# samd21_sensorhub_1_1_1_jan2022.net
KiCad netlist of a schematic drawn in EAGLE
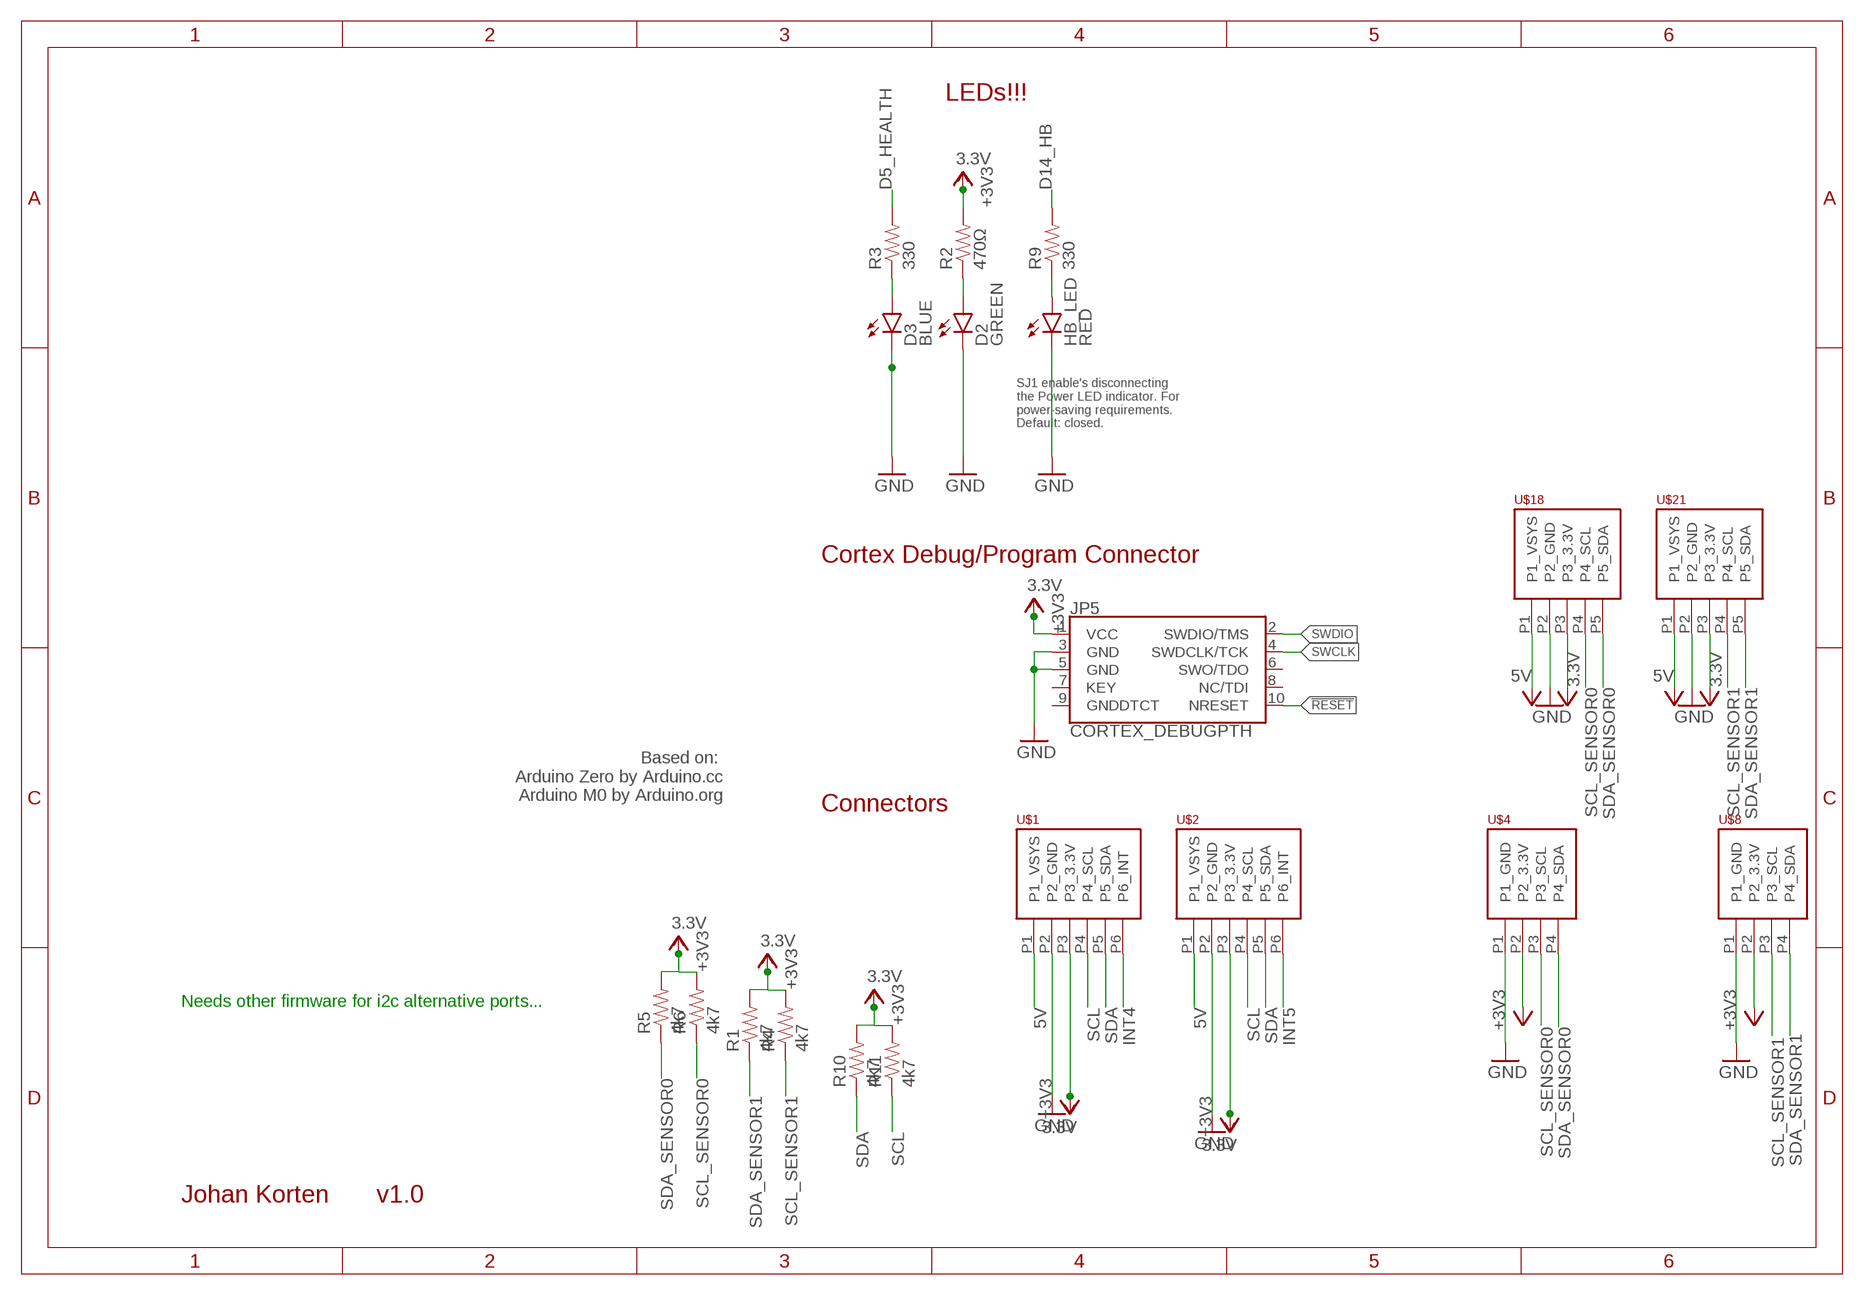
[diagram p0: schematic, sheet 1]
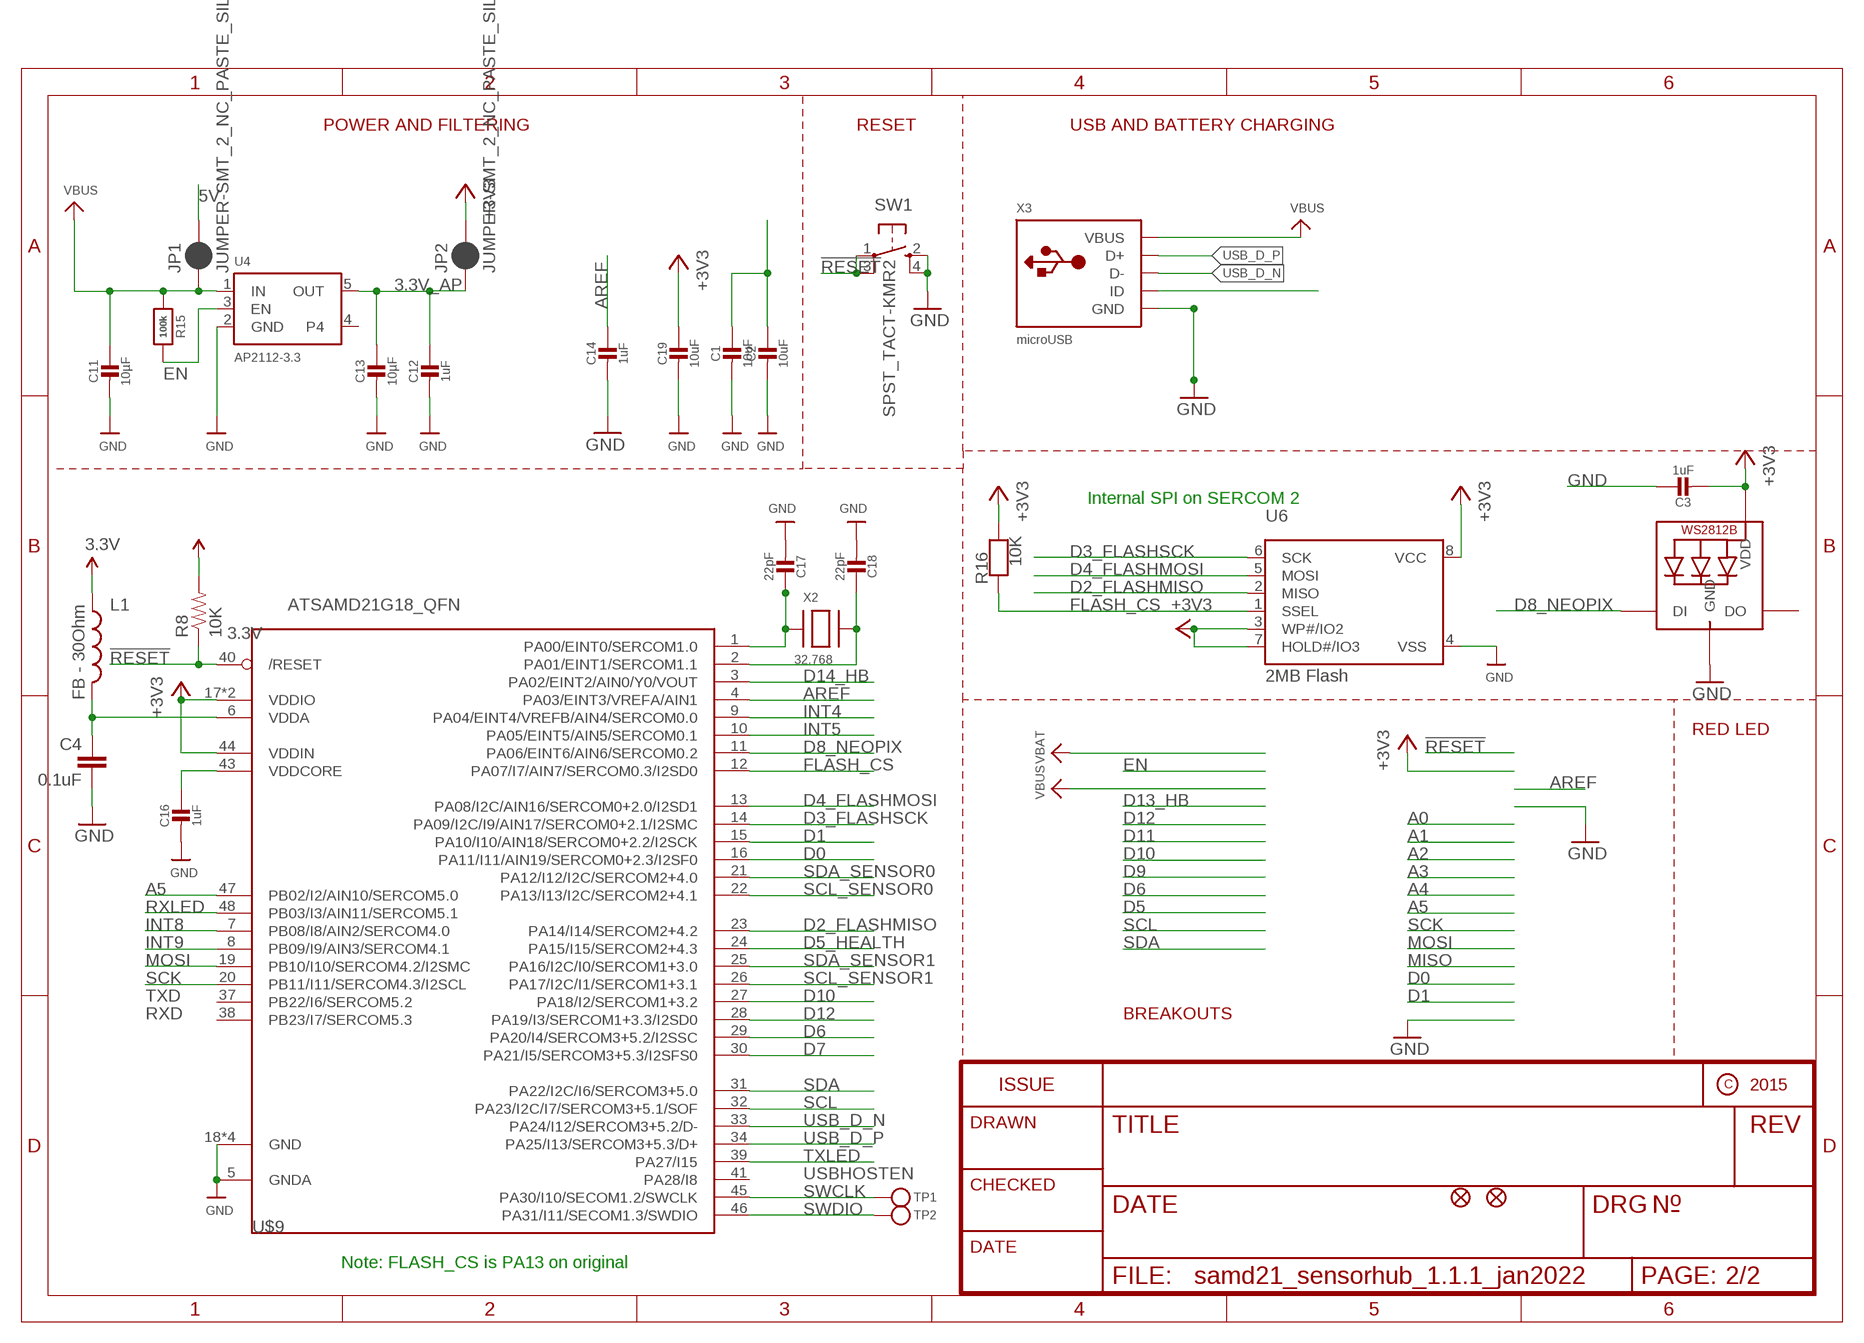
[diagram p1: schematic, sheet 2]

(export (version "E")
  (design (tool "Eeschema 10.0.6"))
  (components
    (comp (ref "D2")
      (value "GREEN")
      (footprint "eagle-import:LED-0603")
      (libsource (lib "eagle-import") (part "LED-RED0603"))
    )
    (comp (ref "D3")
      (value "BLUE")
      (footprint "eagle-import:LED-0603")
      (libsource (lib "eagle-import") (part "LED-BLUE0603"))
    )
    (comp (ref "HB_LED")
      (value "RED")
      (footprint "eagle-import:LED-0603")
      (libsource (lib "eagle-import") (part "LED-RED0603"))
    )
    (comp (ref "JP5")
      (value "CORTEX_DEBUGPTH")
      (footprint "eagle-import:2X5-PTH-1.27MM")
      (libsource (lib "eagle-import") (part "CORTEX_DEBUGPTH"))
    )
    (comp (ref "R1")
      (value "4k7")
      (footprint "eagle-import:0603-RES")
      (libsource (lib "eagle-import") (part "330OHM1/10W1%(0603)"))
    )
    (comp (ref "R2")
      (value "470Ω")
      (footprint "eagle-import:0603-RES")
      (libsource (lib "eagle-import") (part "330OHM1/10W1%(0603)"))
    )
    (comp (ref "R3")
      (value "330")
      (footprint "eagle-import:0603-RES")
      (libsource (lib "eagle-import") (part "330OHM1/10W1%(0603)"))
    )
    (comp (ref "R4")
      (value "4k7")
      (footprint "eagle-import:0603-RES")
      (libsource (lib "eagle-import") (part "330OHM1/10W1%(0603)"))
    )
    (comp (ref "R5")
      (value "4k7")
      (footprint "eagle-import:0603-RES")
      (libsource (lib "eagle-import") (part "330OHM1/10W1%(0603)"))
    )
    (comp (ref "R6")
      (value "4k7")
      (footprint "eagle-import:0603-RES")
      (libsource (lib "eagle-import") (part "330OHM1/10W1%(0603)"))
    )
    (comp (ref "R9")
      (value "330")
      (footprint "eagle-import:0603-RES")
      (libsource (lib "eagle-import") (part "330OHM1/10W1%(0603)"))
    )
    (comp (ref "R10")
      (value "4k7")
      (footprint "eagle-import:0603-RES")
      (libsource (lib "eagle-import") (part "330OHM1/10W1%(0603)"))
    )
    (comp (ref "R11")
      (value "4k7")
      (footprint "eagle-import:0603-RES")
      (libsource (lib "eagle-import") (part "330OHM1/10W1%(0603)"))
    )
    (comp (ref "U$1")
      (value "PHOENIX_PTSM_M6_TH_I2CPPANGLE")
      (footprint "eagle-import:PTSM_M6_THRHOLE")
      (libsource (lib "eagle-import") (part "PHOENIX_PTSM_M6_TH_I2CPPANGLE"))
    )
    (comp (ref "U$2")
      (value "PHOENIX_PTSM_M6_TH_I2CPPANGLE")
      (footprint "eagle-import:PTSM_M6_THRHOLE")
      (libsource (lib "eagle-import") (part "PHOENIX_PTSM_M6_TH_I2CPPANGLE"))
    )
    (comp (ref "U$4")
      (value "PHOENIX_PTSM_M4_THANGLE")
      (footprint "eagle-import:PTSM_M4_TH")
      (libsource (lib "eagle-import") (part "PHOENIX_PTSM_M4_THANGLE"))
    )
    (comp (ref "U$8")
      (value "PHOENIX_PTSM_M4_THANGLE")
      (footprint "eagle-import:PTSM_M4_TH")
      (libsource (lib "eagle-import") (part "PHOENIX_PTSM_M4_THANGLE"))
    )
    (comp (ref "U$18")
      (value "PHOENIX_PTSM_M5_TH_I2C++")
      (footprint "eagle-import:PTSM_M5_THRHOLE")
      (libsource (lib "eagle-import") (part "PHOENIX_PTSM_M5_TH_I2C++"))
    )
    (comp (ref "U$21")
      (value "PHOENIX_PTSM_M5_TH_I2C++")
      (footprint "eagle-import:PTSM_M5_THRHOLE")
      (libsource (lib "eagle-import") (part "PHOENIX_PTSM_M5_TH_I2C++"))
    )
    (comp (ref "C1")
      (value "10uF")
      (footprint "eagle-import:0805-NO")
      (libsource (lib "eagle-import") (part "CAP_CERAMIC0805-NOOUTLINE"))
    )
    (comp (ref "C2")
      (value "10uF")
      (footprint "eagle-import:0805-NO")
      (libsource (lib "eagle-import") (part "CAP_CERAMIC0805-NOOUTLINE"))
    )
    (comp (ref "C3")
      (value "1uF")
      (footprint "eagle-import:0603-NO")
      (libsource (lib "eagle-import") (part "CAP_CERAMIC0603_NO"))
    )
    (comp (ref "C4")
      (value "0.1uF")
      (footprint "eagle-import:0402-CAP")
      (libsource (lib "eagle-import") (part "0.1UF-16V(+-10%)(0402)"))
    )
    (comp (ref "C11")
      (value "10µF")
      (footprint "eagle-import:0805-NO")
      (libsource (lib "eagle-import") (part "CAP_CERAMIC0805-NOOUTLINE"))
    )
    (comp (ref "C12")
      (value "1uF")
      (footprint "eagle-import:0603-NO")
      (libsource (lib "eagle-import") (part "CAP_CERAMIC0603_NO"))
    )
    (comp (ref "C13")
      (value "10µF")
      (footprint "eagle-import:0805-NO")
      (libsource (lib "eagle-import") (part "CAP_CERAMIC0805-NOOUTLINE"))
    )
    (comp (ref "C14")
      (value "1uF")
      (footprint "eagle-import:0603-NO")
      (libsource (lib "eagle-import") (part "CAP_CERAMIC0603_NO"))
    )
    (comp (ref "C16")
      (value "1uF")
      (footprint "eagle-import:0603-NO")
      (libsource (lib "eagle-import") (part "CAP_CERAMIC0603_NO"))
    )
    (comp (ref "C17")
      (value "22pF")
      (footprint "eagle-import:0603-NO")
      (libsource (lib "eagle-import") (part "CAP_CERAMIC0603_NO"))
    )
    (comp (ref "C18")
      (value "22pF")
      (footprint "eagle-import:0603-NO")
      (libsource (lib "eagle-import") (part "CAP_CERAMIC0603_NO"))
    )
    (comp (ref "C19")
      (value "10uF")
      (footprint "eagle-import:0805-NO")
      (libsource (lib "eagle-import") (part "CAP_CERAMIC0805-NOOUTLINE"))
    )
    (comp (ref "JP1")
      (value "JUMPER-SMT_2_NC_PASTE_SILK")
      (footprint "eagle-import:SMT-JUMPER_2_NC_PASTE_SILK")
      (libsource (lib "eagle-import") (part "JUMPER-SMT_2_NC_PASTE_SILK"))
    )
    (comp (ref "JP2")
      (value "JUMPER-SMT_2_NC_PASTE_SILK")
      (footprint "eagle-import:SMT-JUMPER_2_NC_PASTE_SILK")
      (libsource (lib "eagle-import") (part "JUMPER-SMT_2_NC_PASTE_SILK"))
    )
    (comp (ref "L1")
      (value "FB - 30Ohm")
      (footprint "eagle-import:0603")
      (libsource (lib "eagle-import") (part "INDUCTOR0603"))
    )
    (comp (ref "LED1")
      (value "WS2812B3535")
      (footprint "eagle-import:LED3535")
      (libsource (lib "eagle-import") (part "WS2812B3535"))
    )
    (comp (ref "R8")
      (value "10K")
      (footprint "eagle-import:0603-RES")
      (libsource (lib "eagle-import") (part "10KOHM-1/10W-1%(0603)0603"))
    )
    (comp (ref "R15")
      (value "100k")
      (footprint "eagle-import:0603-NO")
      (libsource (lib "eagle-import") (part "RESISTOR_0603_NOOUT"))
    )
    (comp (ref "R16")
      (value "10K")
      (footprint "eagle-import:0603-NO")
      (libsource (lib "eagle-import") (part "RESISTOR_0603_NOOUT"))
    )
    (comp (ref "SW1")
      (value "SPST_TACT-KMR2")
      (footprint "eagle-import:KMR2")
      (libsource (lib "eagle-import") (part "SPST_TACT-KMR2"))
    )
    (comp (ref "TP1")
      (value "TESTPOINTROUND1.5MM")
      (footprint "eagle-import:TESTPOINT_ROUND_1.5MM")
      (libsource (lib "eagle-import") (part "TESTPOINTROUND1.5MM"))
    )
    (comp (ref "TP2")
      (value "TESTPOINTROUND1.5MM")
      (footprint "eagle-import:TESTPOINT_ROUND_1.5MM")
      (libsource (lib "eagle-import") (part "TESTPOINTROUND1.5MM"))
    )
    (comp (ref "U$9")
      (value "ATSAMD21G18_QFN")
      (footprint "eagle-import:TQFN48_7MM")
      (libsource (lib "eagle-import") (part "ATSAMD21G_QFN"))
    )
    (comp (ref "U$34")
      (value "FIDUCIAL\"\"")
      (footprint "eagle-import:FIDUCIAL_1MM")
      (libsource (lib "eagle-import") (part "FIDUCIAL{dblquote}{dblquote}"))
    )
    (comp (ref "U$35")
      (value "FIDUCIAL\"\"")
      (footprint "eagle-import:FIDUCIAL_1MM")
      (libsource (lib "eagle-import") (part "FIDUCIAL{dblquote}{dblquote}"))
    )
    (comp (ref "U4")
      (value "AP2112-3.3")
      (footprint "eagle-import:SOT23-5")
      (libsource (lib "eagle-import") (part "VREG_SOT23-5"))
    )
    (comp (ref "U6")
      (value "2MB Flash")
      (footprint "eagle-import:SOIC8_208MIL")
      (libsource (lib "eagle-import") (part "SPIFLASH_SOIC8208MIL"))
    )
    (comp (ref "X2")
      (value "32.768")
      (footprint "eagle-import:XTAL3215")
      (libsource (lib "eagle-import") (part "XTAL-3.2X1.5"))
    )
    (comp (ref "X3")
      (value "microUSB")
      (footprint "eagle-import:4UCONN_20329_V2")
      (libsource (lib "eagle-import") (part "USB_MICRO_20329_V2"))
    )
  )
  (nets
    (net (code "1") (name "3.3V") (class "Default")
      (node (ref "C19") (pin "1") (pinfunction "1_1") (pintype "passive"))
      (node (ref "C3") (pin "2") (pinfunction "2_2") (pintype "passive"))
      (node (ref "JP2") (pin "2") (pinfunction "2_2") (pintype "passive"))
      (node (ref "JP5") (pin "1") (pinfunction "VCC_1") (pintype "bidirectional"))
      (node (ref "L1") (pin "1") (pinfunction "1_1") (pintype "passive"))
      (node (ref "LED1") (pin "2") (pinfunction "VDD_2") (pintype "power_in"))
      (node (ref "R1") (pin "2") (pinfunction "2_2") (pintype "passive"))
      (node (ref "R10") (pin "2") (pinfunction "2_2") (pintype "passive"))
      (node (ref "R11") (pin "2") (pinfunction "2_2") (pintype "passive"))
      (node (ref "R16") (pin "2") (pinfunction "2_2") (pintype "passive"))
      (node (ref "R2") (pin "2") (pinfunction "2_2") (pintype "passive"))
      (node (ref "R4") (pin "2") (pinfunction "2_2") (pintype "passive"))
      (node (ref "R5") (pin "2") (pinfunction "2_2") (pintype "passive"))
      (node (ref "R6") (pin "2") (pinfunction "2_2") (pintype "passive"))
      (node (ref "R8") (pin "2") (pinfunction "2_2") (pintype "passive"))
      (node (ref "U$1") (pin "P3") (pinfunction "P3_3.3V_P3") (pintype "power_in"))
      (node (ref "U$18") (pin "P3") (pinfunction "P3_3.3V_P3") (pintype "power_in"))
      (node (ref "U$2") (pin "P3") (pinfunction "P3_3.3V_P3") (pintype "power_in"))
      (node (ref "U$21") (pin "P3") (pinfunction "P3_3.3V_P3") (pintype "power_in"))
      (node (ref "U$4") (pin "P2") (pinfunction "P2_3.3V_P2") (pintype "power_in"))
      (node (ref "U$8") (pin "P2") (pinfunction "P2_3.3V_P2") (pintype "power_in"))
      (node (ref "U$9") (pin "17") (pinfunction "VDDIO_17") (pintype "power_in"))
      (node (ref "U$9") (pin "36") (pinfunction "VDDIO_36") (pintype "power_in"))
      (node (ref "U$9") (pin "44") (pinfunction "VDDIN_44") (pintype "power_in"))
      (node (ref "U6") (pin "3") (pinfunction "WP#/IO2_3") (pintype "bidirectional"))
      (node (ref "U6") (pin "7") (pinfunction "HOLD#/IO3_7") (pintype "bidirectional"))
      (node (ref "U6") (pin "8") (pinfunction "VCC_8") (pintype "bidirectional"))
    )
    (net (code "2") (name "3.3V_AP") (class "Default")
      (node (ref "C12") (pin "1") (pinfunction "1_1") (pintype "passive"))
      (node (ref "C13") (pin "1") (pinfunction "1_1") (pintype "passive"))
      (node (ref "JP2") (pin "1") (pinfunction "1_1") (pintype "passive"))
      (node (ref "U4") (pin "5") (pinfunction "OUT_5") (pintype "power_in"))
    )
    (net (code "3") (name "5V") (class "Default")
      (node (ref "C1") (pin "1") (pinfunction "1_1") (pintype "passive"))
      (node (ref "C2") (pin "1") (pinfunction "1_1") (pintype "passive"))
      (node (ref "JP1") (pin "2") (pinfunction "2_2") (pintype "passive"))
      (node (ref "U$1") (pin "P1") (pinfunction "P1_VSYS_P1") (pintype "power_in"))
      (node (ref "U$18") (pin "P1") (pinfunction "P1_VSYS_P1") (pintype "power_in"))
      (node (ref "U$2") (pin "P1") (pinfunction "P1_VSYS_P1") (pintype "power_in"))
      (node (ref "U$21") (pin "P1") (pinfunction "P1_VSYS_P1") (pintype "power_in"))
    )
    (net (code "9") (name "A5") (class "Default")
      (node (ref "U$9") (pin "47") (pinfunction "PB02/I2/AIN10/SERCOM5.0_47") (pintype "bidirectional"))
    )
    (net (code "10") (name "AREF") (class "Default")
      (node (ref "C14") (pin "1") (pinfunction "1_1") (pintype "passive"))
      (node (ref "U$9") (pin "4") (pinfunction "PA03/EINT3/VREFA/AIN1_4") (pintype "bidirectional"))
    )
    (net (code "11") (name "D0") (class "Default")
      (node (ref "U$9") (pin "16") (pinfunction "PA11/I11/AIN19/SERCOM0+2.3/I2SF0_16") (pintype "bidirectional"))
    )
    (net (code "12") (name "D1") (class "Default")
      (node (ref "U$9") (pin "15") (pinfunction "PA10/I10/AIN18/SERCOM0+2.2/I2SCK_15") (pintype "bidirectional"))
    )
    (net (code "13") (name "D2_FLASHMISO") (class "Default")
      (node (ref "U$9") (pin "23") (pinfunction "PA14/I14/SERCOM2+4.2_23") (pintype "bidirectional"))
      (node (ref "U6") (pin "2") (pinfunction "MISO_2") (pintype "bidirectional"))
    )
    (net (code "14") (name "D3_FLASHSCK") (class "Default")
      (node (ref "U$9") (pin "14") (pinfunction "PA09/I2C/I9/AIN17/SERCOM0+2.1/I2SMC_14") (pintype "bidirectional"))
      (node (ref "U6") (pin "6") (pinfunction "SCK_6") (pintype "bidirectional"))
    )
    (net (code "15") (name "D4_FLASHMOSI") (class "Default")
      (node (ref "U$9") (pin "13") (pinfunction "PA08/I2C/AIN16/SERCOM0+2.0/I2SD1_13") (pintype "bidirectional"))
      (node (ref "U6") (pin "5") (pinfunction "MOSI_5") (pintype "bidirectional"))
    )
    (net (code "17") (name "D5_HEALTH") (class "Default")
      (node (ref "R3") (pin "2") (pinfunction "2_2") (pintype "passive"))
      (node (ref "U$9") (pin "24") (pinfunction "PA15/I15/SERCOM2+4.3_24") (pintype "bidirectional"))
    )
    (net (code "18") (name "D6") (class "Default")
      (node (ref "U$9") (pin "29") (pinfunction "PA20/I4/SERCOM3+5.2/I2SSC_29") (pintype "bidirectional"))
    )
    (net (code "19") (name "D7") (class "Default")
      (node (ref "U$9") (pin "30") (pinfunction "PA21/I5/SERCOM3+5.3/I2SFS0_30") (pintype "bidirectional"))
    )
    (net (code "20") (name "D8_NEOPIX") (class "Default")
      (node (ref "LED1") (pin "1") (pinfunction "DI_1") (pintype "input"))
      (node (ref "U$9") (pin "11") (pinfunction "PA06/EINT6/AIN6/SERCOM0.2_11") (pintype "bidirectional"))
    )
    (net (code "22") (name "D10") (class "Default")
      (node (ref "U$9") (pin "27") (pinfunction "PA18/I2/SERCOM1+3.2_27") (pintype "bidirectional"))
    )
    (net (code "24") (name "D12") (class "Default")
      (node (ref "U$9") (pin "28") (pinfunction "PA19/I3/SERCOM1+3.3/I2SD0_28") (pintype "bidirectional"))
    )
    (net (code "26") (name "D14_HB") (class "Default")
      (node (ref "R9") (pin "2") (pinfunction "2_2") (pintype "passive"))
      (node (ref "U$9") (pin "3") (pinfunction "PA02/EINT2/AIN0/Y0/VOUT_3") (pintype "bidirectional"))
    )
    (net (code "27") (name "EN") (class "Default")
      (node (ref "R15") (pin "2") (pinfunction "2_2") (pintype "passive"))
      (node (ref "U4") (pin "3") (pinfunction "EN_3") (pintype "input"))
    )
    (net (code "28") (name "FLASH_CS") (class "Default")
      (node (ref "R16") (pin "1") (pinfunction "1_1") (pintype "passive"))
      (node (ref "U$9") (pin "12") (pinfunction "PA07/I7/AIN7/SERCOM0.3/I2SD0_12") (pintype "bidirectional"))
      (node (ref "U6") (pin "1") (pinfunction "SSEL_1") (pintype "bidirectional"))
    )
    (net (code "29") (name "GND") (class "Default")
      (node (ref "C1") (pin "2") (pinfunction "2_2") (pintype "passive"))
      (node (ref "C11") (pin "2") (pinfunction "2_2") (pintype "passive"))
      (node (ref "C12") (pin "2") (pinfunction "2_2") (pintype "passive"))
      (node (ref "C13") (pin "2") (pinfunction "2_2") (pintype "passive"))
      (node (ref "C14") (pin "2") (pinfunction "2_2") (pintype "passive"))
      (node (ref "C16") (pin "2") (pinfunction "2_2") (pintype "passive"))
      (node (ref "C17") (pin "2") (pinfunction "2_2") (pintype "passive"))
      (node (ref "C18") (pin "2") (pinfunction "2_2") (pintype "passive"))
      (node (ref "C19") (pin "2") (pinfunction "2_2") (pintype "passive"))
      (node (ref "C2") (pin "2") (pinfunction "2_2") (pintype "passive"))
      (node (ref "C3") (pin "1") (pinfunction "1_1") (pintype "passive"))
      (node (ref "C4") (pin "2") (pinfunction "2_2") (pintype "passive"))
      (node (ref "D2") (pin "C") (pinfunction "C_C") (pintype "passive"))
      (node (ref "D3") (pin "C") (pinfunction "C_C") (pintype "passive"))
      (node (ref "HB_LED") (pin "C") (pinfunction "C_C") (pintype "passive"))
      (node (ref "JP5") (pin "3") (pinfunction "GND_3") (pintype "bidirectional"))
      (node (ref "JP5") (pin "5") (pinfunction "GND_5") (pintype "bidirectional"))
      (node (ref "LED1") (pin "4") (pinfunction "GND_4") (pintype "power_in"))
      (node (ref "SW1") (pin "2") (pinfunction "S_2") (pintype "passive"))
      (node (ref "SW1") (pin "4") (pinfunction "S1_4") (pintype "passive"))
      (node (ref "U$1") (pin "P2") (pinfunction "P2_GND_P2") (pintype "power_in"))
      (node (ref "U$18") (pin "P2") (pinfunction "P2_GND_P2") (pintype "power_in"))
      (node (ref "U$2") (pin "P2") (pinfunction "P2_GND_P2") (pintype "power_in"))
      (node (ref "U$21") (pin "P2") (pinfunction "P2_GND_P2") (pintype "power_in"))
      (node (ref "U$4") (pin "P1") (pinfunction "P1_GND_P1") (pintype "power_in"))
      (node (ref "U$8") (pin "P1") (pinfunction "P1_GND_P1") (pintype "power_in"))
      (node (ref "U$9") (pin "18") (pinfunction "GND_18") (pintype "power_in"))
      (node (ref "U$9") (pin "35") (pinfunction "GND_35") (pintype "power_in"))
      (node (ref "U$9") (pin "42") (pinfunction "GND_42") (pintype "power_in"))
      (node (ref "U$9") (pin "5") (pinfunction "GNDA_5") (pintype "power_in"))
      (node (ref "U$9") (pin "THERMAL") (pinfunction "GND_THERMAL") (pintype "power_in"))
      (node (ref "U4") (pin "2") (pinfunction "GND_2") (pintype "power_in"))
      (node (ref "U6") (pin "4") (pinfunction "VSS_4") (pintype "bidirectional"))
      (node (ref "X3") (pin "BASE@1") (pinfunction "GND_BASE@1") (pintype "power_in"))
      (node (ref "X3") (pin "BASE@2") (pinfunction "GND_BASE@2") (pintype "power_in"))
      (node (ref "X3") (pin "GND") (pinfunction "GND_GND") (pintype "power_in"))
      (node (ref "X3") (pin "SPRT@1") (pinfunction "GND_SPRT@1") (pintype "power_in"))
      (node (ref "X3") (pin "SPRT@2") (pinfunction "GND_SPRT@2") (pintype "power_in"))
      (node (ref "X3") (pin "SPRT@3") (pinfunction "GND_SPRT@3") (pintype "power_in"))
      (node (ref "X3") (pin "SPRT@4") (pinfunction "GND_SPRT@4") (pintype "power_in"))
    )
    (net (code "30") (name "INT4") (class "Default")
      (node (ref "U$1") (pin "P6") (pinfunction "P6_INT_P6") (pintype "power_in"))
      (node (ref "U$9") (pin "9") (pinfunction "PA04/EINT4/VREFB/AIN4/SERCOM0.0_9") (pintype "bidirectional"))
    )
    (net (code "31") (name "INT5") (class "Default")
      (node (ref "U$2") (pin "P6") (pinfunction "P6_INT_P6") (pintype "power_in"))
      (node (ref "U$9") (pin "10") (pinfunction "PA05/EINT5/AIN5/SERCOM0.1_10") (pintype "bidirectional"))
    )
    (net (code "32") (name "INT8") (class "Default")
      (node (ref "U$9") (pin "7") (pinfunction "PB08/I8/AIN2/SERCOM4.0_7") (pintype "bidirectional"))
    )
    (net (code "33") (name "INT9") (class "Default")
      (node (ref "U$9") (pin "8") (pinfunction "PB09/I9/AIN3/SERCOM4.1_8") (pintype "bidirectional"))
    )
    (net (code "35") (name "MOSI") (class "Default")
      (node (ref "U$9") (pin "19") (pinfunction "PB10/I10/SERCOM4.2/I2SMC_19") (pintype "bidirectional"))
    )
    (net (code "36") (name "Net-(D2-PadA)") (class "Default")
      (node (ref "D2") (pin "A") (pinfunction "A_A") (pintype "passive"))
      (node (ref "R2") (pin "1") (pinfunction "1_1") (pintype "passive"))
    )
    (net (code "37") (name "Net-(D3-PadA)") (class "Default")
      (node (ref "D3") (pin "A") (pinfunction "A_A") (pintype "passive"))
      (node (ref "R3") (pin "1") (pinfunction "1_1") (pintype "passive"))
    )
    (net (code "38") (name "Net-(HB_LED-PadA)") (class "Default")
      (node (ref "HB_LED") (pin "A") (pinfunction "A_A") (pintype "passive"))
      (node (ref "R9") (pin "1") (pinfunction "1_1") (pintype "passive"))
    )
    (net (code "39") (name "Net-(U$9-PA00{slash}EINT0{slash}SERCOM1.0)") (class "Default")
      (node (ref "C17") (pin "1") (pinfunction "1_1") (pintype "passive"))
      (node (ref "U$9") (pin "1") (pinfunction "PA00/EINT0/SERCOM1.0_1") (pintype "bidirectional"))
      (node (ref "X2") (pin "P$1") (pinfunction "P$1_P$1") (pintype "bidirectional"))
    )
    (net (code "40") (name "Net-(U$9-PA01{slash}EINT1{slash}SERCOM1.1)") (class "Default")
      (node (ref "C18") (pin "1") (pinfunction "1_1") (pintype "passive"))
      (node (ref "U$9") (pin "2") (pinfunction "PA01/EINT1/SERCOM1.1_2") (pintype "bidirectional"))
      (node (ref "X2") (pin "P$2") (pinfunction "P$2_P$2") (pintype "bidirectional"))
    )
    (net (code "41") (name "Net-(U$9-VDDA)") (class "Default")
      (node (ref "C4") (pin "1") (pinfunction "1_1") (pintype "passive"))
      (node (ref "L1") (pin "2") (pinfunction "2_2") (pintype "passive"))
      (node (ref "U$9") (pin "6") (pinfunction "VDDA_6") (pintype "power_in"))
    )
    (net (code "42") (name "Net-(U$9-VDDCORE)") (class "Default")
      (node (ref "C16") (pin "1") (pinfunction "1_1") (pintype "passive"))
      (node (ref "U$9") (pin "43") (pinfunction "VDDCORE_43") (pintype "power_in"))
    )
    (net (code "43") (name "RXLED") (class "Default")
      (node (ref "U$9") (pin "48") (pinfunction "PB03/I3/AIN11/SERCOM5.1_48") (pintype "bidirectional"))
    )
    (net (code "44") (name "SCK") (class "Default")
      (node (ref "U$9") (pin "20") (pinfunction "PB11/I11/SERCOM4.3/I2SCL_20") (pintype "bidirectional"))
    )
    (net (code "45") (name "SCL") (class "Default")
      (node (ref "R11") (pin "1") (pinfunction "1_1") (pintype "passive"))
      (node (ref "U$1") (pin "P4") (pinfunction "P4_SCL_P4") (pintype "bidirectional"))
      (node (ref "U$2") (pin "P4") (pinfunction "P4_SCL_P4") (pintype "bidirectional"))
      (node (ref "U$9") (pin "32") (pinfunction "PA23/I2C/I7/SERCOM3+5.1/SOF_32") (pintype "bidirectional"))
    )
    (net (code "46") (name "SCL_SENSOR0") (class "Default")
      (node (ref "R6") (pin "1") (pinfunction "1_1") (pintype "passive"))
      (node (ref "U$18") (pin "P4") (pinfunction "P4_SCL_P4") (pintype "bidirectional"))
      (node (ref "U$4") (pin "P3") (pinfunction "P3_SCL_P3") (pintype "bidirectional"))
      (node (ref "U$9") (pin "22") (pinfunction "PA13/I13/I2C/SERCOM2+4.1_22") (pintype "bidirectional"))
    )
    (net (code "47") (name "SCL_SENSOR1") (class "Default")
      (node (ref "R4") (pin "1") (pinfunction "1_1") (pintype "passive"))
      (node (ref "U$21") (pin "P4") (pinfunction "P4_SCL_P4") (pintype "bidirectional"))
      (node (ref "U$8") (pin "P3") (pinfunction "P3_SCL_P3") (pintype "bidirectional"))
      (node (ref "U$9") (pin "26") (pinfunction "PA17/I2C/I1/SERCOM1+3.1_26") (pintype "bidirectional"))
    )
    (net (code "48") (name "SDA") (class "Default")
      (node (ref "R10") (pin "1") (pinfunction "1_1") (pintype "passive"))
      (node (ref "U$1") (pin "P5") (pinfunction "P5_SDA_P5") (pintype "bidirectional"))
      (node (ref "U$2") (pin "P5") (pinfunction "P5_SDA_P5") (pintype "bidirectional"))
      (node (ref "U$9") (pin "31") (pinfunction "PA22/I2C/I6/SERCOM3+5.0_31") (pintype "bidirectional"))
    )
    (net (code "49") (name "SDA_SENSOR0") (class "Default")
      (node (ref "R5") (pin "1") (pinfunction "1_1") (pintype "passive"))
      (node (ref "U$18") (pin "P5") (pinfunction "P5_SDA_P5") (pintype "bidirectional"))
      (node (ref "U$4") (pin "P4") (pinfunction "P4_SDA_P4") (pintype "bidirectional"))
      (node (ref "U$9") (pin "21") (pinfunction "PA12/I12/I2C/SERCOM2+4.0_21") (pintype "bidirectional"))
    )
    (net (code "50") (name "SDA_SENSOR1") (class "Default")
      (node (ref "R1") (pin "1") (pinfunction "1_1") (pintype "passive"))
      (node (ref "U$21") (pin "P5") (pinfunction "P5_SDA_P5") (pintype "bidirectional"))
      (node (ref "U$8") (pin "P4") (pinfunction "P4_SDA_P4") (pintype "bidirectional"))
      (node (ref "U$9") (pin "25") (pinfunction "PA16/I2C/I0/SERCOM1+3.0_25") (pintype "bidirectional"))
    )
    (net (code "51") (name "SWCLK") (class "Default")
      (node (ref "JP5") (pin "4") (pinfunction "SWDCLK/TCK_4") (pintype "bidirectional"))
      (node (ref "TP1") (pin "P$1") (pinfunction "P$1_P$1") (pintype "bidirectional"))
      (node (ref "U$9") (pin "45") (pinfunction "PA30/I10/SECOM1.2/SWCLK_45") (pintype "bidirectional"))
    )
    (net (code "52") (name "SWDIO") (class "Default")
      (node (ref "JP5") (pin "2") (pinfunction "SWDIO/TMS_2") (pintype "bidirectional"))
      (node (ref "TP2") (pin "P$1") (pinfunction "P$1_P$1") (pintype "bidirectional"))
      (node (ref "U$9") (pin "46") (pinfunction "PA31/I11/SECOM1.3/SWDIO_46") (pintype "bidirectional"))
    )
    (net (code "53") (name "TXLED") (class "Default")
      (node (ref "U$9") (pin "39") (pinfunction "PA27/I15_39") (pintype "bidirectional"))
    )
    (net (code "54") (name "USB_D_N") (class "Default")
      (node (ref "U$9") (pin "33") (pinfunction "PA24/I12/SERCOM3+5.2/D-_33") (pintype "bidirectional"))
      (node (ref "X3") (pin "D-") (pinfunction "D-_D-") (pintype "bidirectional"))
    )
    (net (code "55") (name "USB_D_P") (class "Default")
      (node (ref "U$9") (pin "34") (pinfunction "PA25/I13/SERCOM3+5.3/D+_34") (pintype "bidirectional"))
      (node (ref "X3") (pin "D+") (pinfunction "D+_D+") (pintype "bidirectional"))
    )
    (net (code "57") (name "VBUS") (class "Default")
      (node (ref "C11") (pin "1") (pinfunction "1_1") (pintype "passive"))
      (node (ref "JP1") (pin "1") (pinfunction "1_1") (pintype "passive"))
      (node (ref "R15") (pin "1") (pinfunction "1_1") (pintype "passive"))
      (node (ref "U4") (pin "1") (pinfunction "IN_1") (pintype "power_in"))
      (node (ref "X3") (pin "VBUS") (pinfunction "VBUS_VBUS") (pintype "power_in"))
    )
    (net (code "58") (name "unconnected-(JP5-GNDDTCT-Pad9)") (class "Default")
      (node (ref "JP5") (pin "9") (pinfunction "GNDDTCT_9") (pintype "bidirectional"))
    )
    (net (code "59") (name "unconnected-(JP5-KEY-Pad7)") (class "Default")
      (node (ref "JP5") (pin "7") (pinfunction "KEY_7") (pintype "bidirectional"))
    )
    (net (code "60") (name "unconnected-(JP5-NC{slash}TDI-Pad8)") (class "Default")
      (node (ref "JP5") (pin "8") (pinfunction "NC/TDI_8") (pintype "bidirectional"))
    )
    (net (code "61") (name "unconnected-(JP5-SWO{slash}TDO-Pad6)") (class "Default")
      (node (ref "JP5") (pin "6") (pinfunction "SWO/TDO_6") (pintype "bidirectional"))
    )
    (net (code "62") (name "unconnected-(LED1-DO-Pad3)") (class "Default")
      (node (ref "LED1") (pin "3") (pinfunction "DO_3") (pintype "output"))
    )
    (net (code "63") (name "unconnected-(U$9-PA28{slash}I8-Pad41)") (class "Default")
      (node (ref "U$9") (pin "41") (pinfunction "PA28/I8_41") (pintype "bidirectional"))
    )
    (net (code "64") (name "unconnected-(U$9-PB22{slash}I6{slash}SERCOM5.2-Pad37)") (class "Default")
      (node (ref "U$9") (pin "37") (pinfunction "PB22/I6/SERCOM5.2_37") (pintype "bidirectional"))
    )
    (net (code "65") (name "unconnected-(U$9-PB23{slash}I7{slash}SERCOM5.3-Pad38)") (class "Default")
      (node (ref "U$9") (pin "38") (pinfunction "PB23/I7/SERCOM5.3_38") (pintype "bidirectional"))
    )
    (net (code "66") (name "unconnected-(U4-P4-Pad4)") (class "Default")
      (node (ref "U4") (pin "4") (pinfunction "P4_4") (pintype "bidirectional"))
    )
    (net (code "67") (name "unconnected-(X3-PadID)") (class "Default")
      (node (ref "X3") (pin "ID") (pinfunction "ID_ID") (pintype "bidirectional"))
    )
    (net (code "68") (name "~{RESET}") (class "Default")
      (node (ref "JP5") (pin "10") (pinfunction "NRESET_10") (pintype "bidirectional"))
      (node (ref "R8") (pin "1") (pinfunction "1_1") (pintype "passive"))
      (node (ref "SW1") (pin "1") (pinfunction "P_1") (pintype "passive"))
      (node (ref "SW1") (pin "3") (pinfunction "P1_3") (pintype "passive"))
      (node (ref "U$9") (pin "40") (pinfunction "/RESET_40") (pintype "bidirectional"))
    )
  )
)
